# display.net
KiCad netlist of a schematic drawn in EAGLE
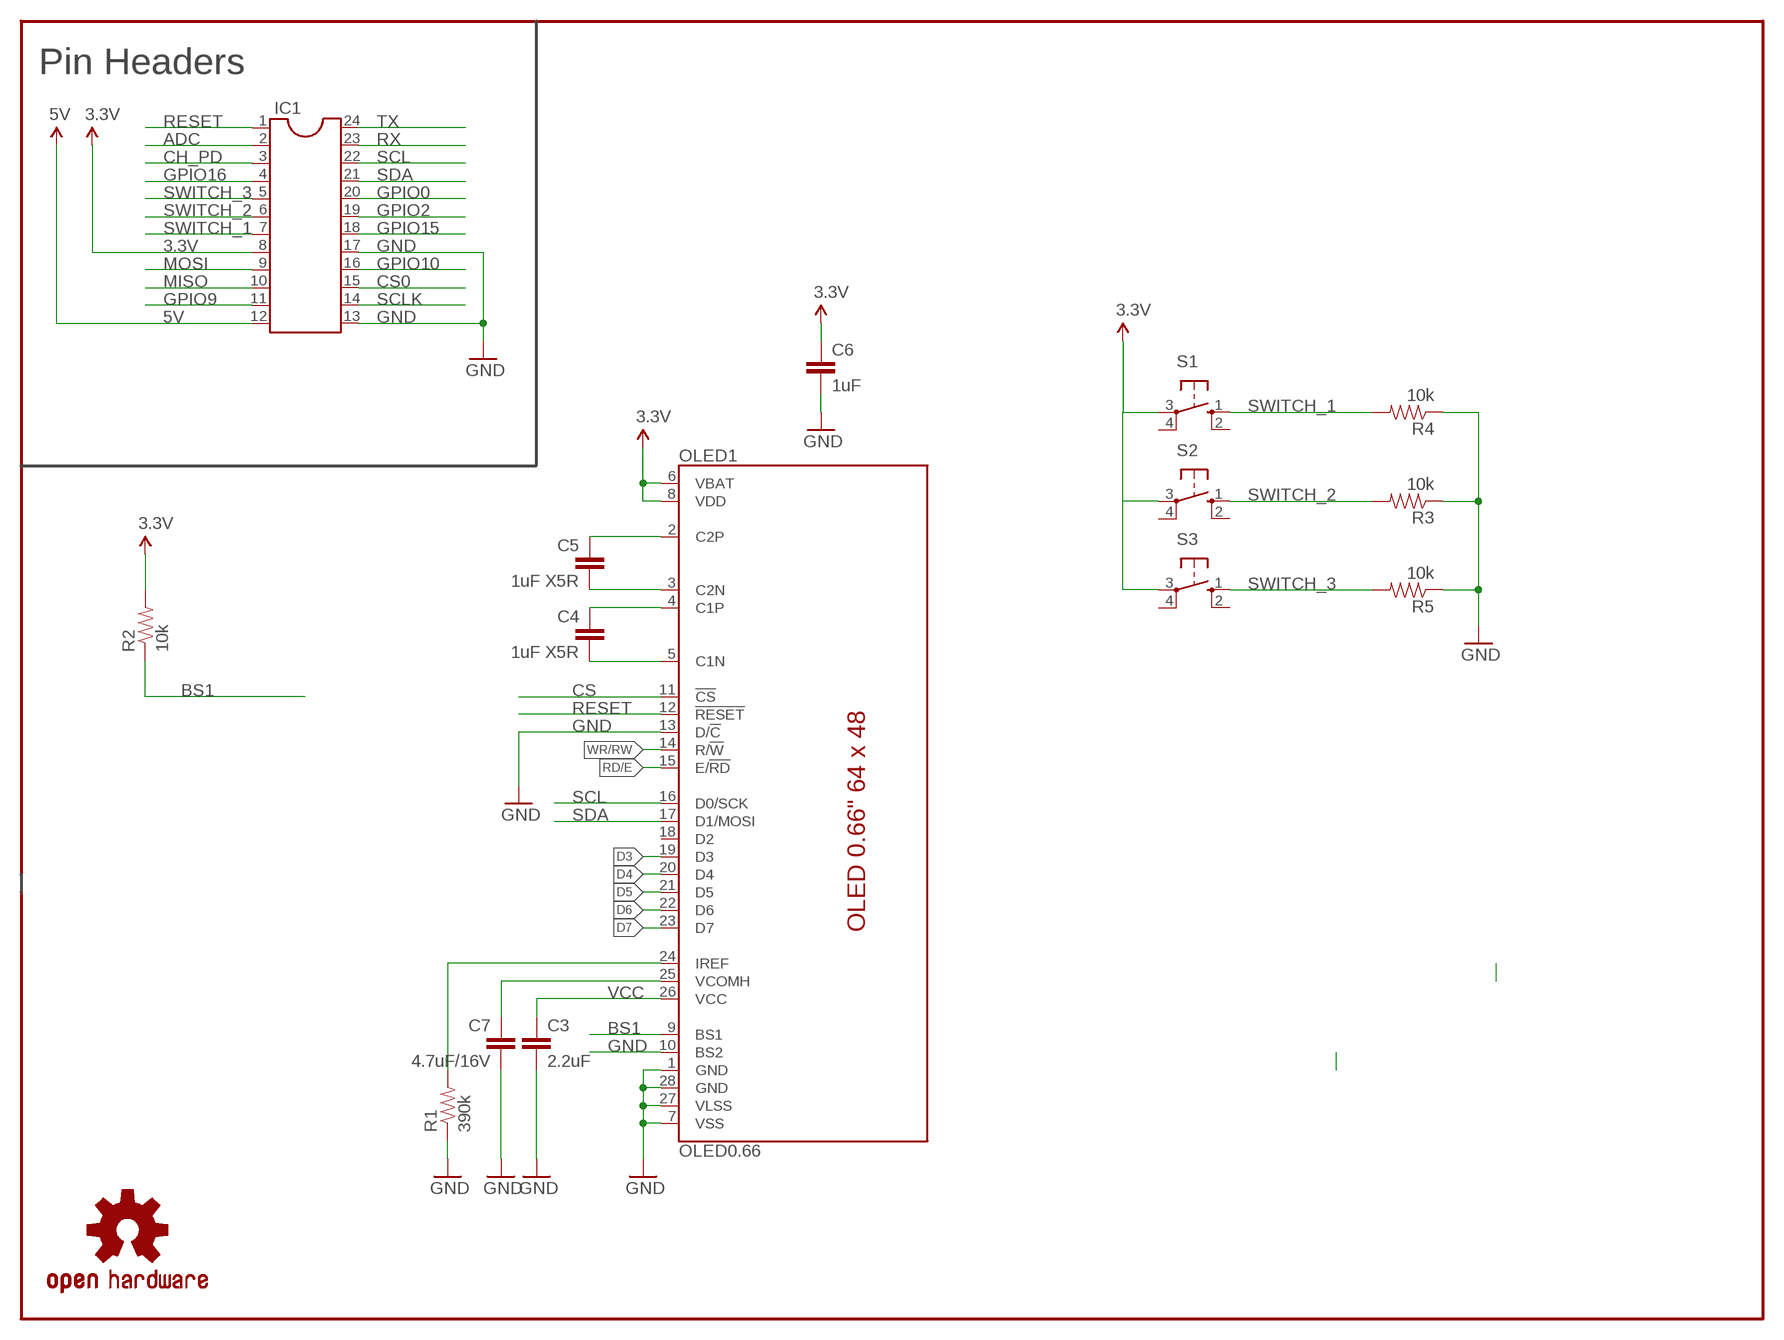
[diagram p0: schematic, sheet 1]

(export (version "E")
  (design (tool "Eeschema 10.0.6"))
  (components
    (comp (ref "C3")
      (value "2.2uF")
      (footprint "eagle-import:1206")
      (libsource (lib "eagle-import") (part "CAP1206"))
    )
    (comp (ref "C4")
      (value "1uF X5R")
      (footprint "eagle-import:1206")
      (libsource (lib "eagle-import") (part "CAP1206"))
    )
    (comp (ref "C5")
      (value "1uF X5R")
      (footprint "eagle-import:1206")
      (libsource (lib "eagle-import") (part "CAP1206"))
    )
    (comp (ref "C6")
      (value "1uF")
      (footprint "eagle-import:1206")
      (libsource (lib "eagle-import") (part "CAP1206"))
    )
    (comp (ref "C7")
      (value "4.7uF/16V")
      (footprint "eagle-import:1206")
      (libsource (lib "eagle-import") (part "CAP1206"))
    )
    (comp (ref "FRAME1")
      (value "FRAME-LETTERNO_PACKAGE")
      (footprint "eagle-import:DUMMY")
      (fields (field (name "DESIGNER") "Nobody"))
      (libsource (lib "eagle-import") (part "FRAME-LETTERNO_PACKAGE"))
    )
    (comp (ref "IC1")
      (value "DIL24-9")
      (footprint "eagle-import:DIL24-9")
      (libsource (lib "eagle-import") (part "DIL24-9"))
    )
    (comp (ref "LOGO1")
      (value "OSHW-LOGOS")
      (footprint "eagle-import:OSHW-LOGO-S")
      (libsource (lib "eagle-import") (part "OSHW-LOGOS"))
    )
    (comp (ref "OLED1")
      (value "OLED0.66")
      (footprint "eagle-import:OLED-0.66-64X48")
      (libsource (lib "eagle-import") (part "OLED0.66"))
    )
    (comp (ref "R1")
      (value "390k")
      (footprint "eagle-import:1206")
      (libsource (lib "eagle-import") (part "RESISTOR1206"))
    )
    (comp (ref "R2")
      (value "10k")
      (footprint "eagle-import:1206")
      (libsource (lib "eagle-import") (part "RESISTOR1206"))
    )
    (comp (ref "R3")
      (value "10k")
      (footprint "eagle-import:1206")
      (libsource (lib "eagle-import") (part "RESISTOR1206"))
    )
    (comp (ref "R4")
      (value "10k")
      (footprint "eagle-import:1206")
      (libsource (lib "eagle-import") (part "RESISTOR1206"))
    )
    (comp (ref "R5")
      (value "10k")
      (footprint "eagle-import:1206")
      (libsource (lib "eagle-import") (part "RESISTOR1206"))
    )
    (comp (ref "S1")
      (value "10-XX")
      (footprint "eagle-import:B3F-10XX")
      (fields (field (name "MPN") "B3F-1000"))
      (libsource (lib "eagle-import") (part "10-XX"))
    )
    (comp (ref "S2")
      (value "10-XX")
      (footprint "eagle-import:B3F-10XX")
      (fields (field (name "MPN") "B3F-1000"))
      (libsource (lib "eagle-import") (part "10-XX"))
    )
    (comp (ref "S3")
      (value "10-XX")
      (footprint "eagle-import:B3F-10XX")
      (fields (field (name "MPN") "B3F-1000"))
      (libsource (lib "eagle-import") (part "10-XX"))
    )
  )
  (nets
    (net (code "1") (name "/ADC") (class "Default")
      (node (ref "IC1") (pin "2") (pinfunction "2_2") (pintype "passive"))
    )
    (net (code "2") (name "/BS1") (class "Default")
      (node (ref "OLED1") (pin "9") (pinfunction "BS1_9") (pintype "bidirectional"))
      (node (ref "R2") (pin "1") (pinfunction "1_1") (pintype "passive"))
    )
    (net (code "3") (name "/CH_PD") (class "Default")
      (node (ref "IC1") (pin "3") (pinfunction "3_3") (pintype "passive"))
    )
    (net (code "4") (name "/CS") (class "Default")
      (node (ref "OLED1") (pin "11") (pinfunction "~{CS}_11") (pintype "bidirectional"))
    )
    (net (code "5") (name "/CS0") (class "Default")
      (node (ref "IC1") (pin "15") (pinfunction "15_15") (pintype "passive"))
    )
    (net (code "6") (name "/GPIO0") (class "Default")
      (node (ref "IC1") (pin "20") (pinfunction "20_20") (pintype "passive"))
    )
    (net (code "7") (name "/GPIO2") (class "Default")
      (node (ref "IC1") (pin "19") (pinfunction "19_19") (pintype "passive"))
    )
    (net (code "8") (name "/GPIO9") (class "Default")
      (node (ref "IC1") (pin "11") (pinfunction "11_11") (pintype "passive"))
    )
    (net (code "9") (name "/GPIO10") (class "Default")
      (node (ref "IC1") (pin "16") (pinfunction "16_16") (pintype "passive"))
    )
    (net (code "10") (name "/GPIO15") (class "Default")
      (node (ref "IC1") (pin "18") (pinfunction "18_18") (pintype "passive"))
    )
    (net (code "11") (name "/GPIO16") (class "Default")
      (node (ref "IC1") (pin "4") (pinfunction "4_4") (pintype "passive"))
    )
    (net (code "12") (name "/MISO") (class "Default")
      (node (ref "IC1") (pin "10") (pinfunction "10_10") (pintype "passive"))
    )
    (net (code "13") (name "/MOSI") (class "Default")
      (node (ref "IC1") (pin "9") (pinfunction "9_9") (pintype "passive"))
    )
    (net (code "14") (name "/RESET") (class "Default")
      (node (ref "IC1") (pin "1") (pinfunction "1_1") (pintype "passive"))
      (node (ref "OLED1") (pin "12") (pinfunction "~{RESET}_12") (pintype "bidirectional"))
    )
    (net (code "15") (name "/RX") (class "Default")
      (node (ref "IC1") (pin "23") (pinfunction "23_23") (pintype "passive"))
    )
    (net (code "16") (name "/SCL") (class "Default")
      (node (ref "IC1") (pin "22") (pinfunction "22_22") (pintype "passive"))
      (node (ref "OLED1") (pin "16") (pinfunction "D0/SCK_16") (pintype "bidirectional"))
    )
    (net (code "17") (name "/SCLK") (class "Default")
      (node (ref "IC1") (pin "14") (pinfunction "14_14") (pintype "passive"))
    )
    (net (code "18") (name "/SDA") (class "Default")
      (node (ref "IC1") (pin "21") (pinfunction "21_21") (pintype "passive"))
      (node (ref "OLED1") (pin "17") (pinfunction "D1/MOSI_17") (pintype "bidirectional"))
    )
    (net (code "19") (name "/SWITCH_1") (class "Default")
      (node (ref "IC1") (pin "7") (pinfunction "7_7") (pintype "passive"))
      (node (ref "R4") (pin "2") (pinfunction "2_2") (pintype "passive"))
      (node (ref "S1") (pin "1") (pinfunction "S_1") (pintype "passive"))
    )
    (net (code "20") (name "/SWITCH_2") (class "Default")
      (node (ref "IC1") (pin "6") (pinfunction "6_6") (pintype "passive"))
      (node (ref "R3") (pin "2") (pinfunction "2_2") (pintype "passive"))
      (node (ref "S2") (pin "1") (pinfunction "S_1") (pintype "passive"))
    )
    (net (code "21") (name "/SWITCH_3") (class "Default")
      (node (ref "IC1") (pin "5") (pinfunction "5_5") (pintype "passive"))
      (node (ref "R5") (pin "2") (pinfunction "2_2") (pintype "passive"))
      (node (ref "S3") (pin "1") (pinfunction "S_1") (pintype "passive"))
    )
    (net (code "22") (name "/TX") (class "Default")
      (node (ref "IC1") (pin "24") (pinfunction "24_24") (pintype "passive"))
    )
    (net (code "23") (name "/VCC") (class "Default")
      (node (ref "C3") (pin "1") (pinfunction "1_1") (pintype "passive"))
      (node (ref "OLED1") (pin "26") (pinfunction "VCC_26") (pintype "bidirectional"))
    )
    (net (code "24") (name "3.3V") (class "Default")
      (node (ref "C6") (pin "1") (pinfunction "1_1") (pintype "passive"))
      (node (ref "IC1") (pin "8") (pinfunction "8_8") (pintype "passive"))
      (node (ref "OLED1") (pin "6") (pinfunction "VBAT_6") (pintype "bidirectional"))
      (node (ref "OLED1") (pin "8") (pinfunction "VDD_8") (pintype "bidirectional"))
      (node (ref "R2") (pin "2") (pinfunction "2_2") (pintype "passive"))
      (node (ref "S1") (pin "3") (pinfunction "P_3") (pintype "passive"))
      (node (ref "S2") (pin "3") (pinfunction "P_3") (pintype "passive"))
      (node (ref "S3") (pin "3") (pinfunction "P_3") (pintype "passive"))
    )
    (net (code "25") (name "5V") (class "Default")
      (node (ref "IC1") (pin "12") (pinfunction "12_12") (pintype "passive"))
    )
    (net (code "26") (name "D3") (class "Default")
      (node (ref "OLED1") (pin "19") (pinfunction "D3_19") (pintype "bidirectional"))
    )
    (net (code "27") (name "D4") (class "Default")
      (node (ref "OLED1") (pin "20") (pinfunction "D4_20") (pintype "bidirectional"))
    )
    (net (code "28") (name "D5") (class "Default")
      (node (ref "OLED1") (pin "21") (pinfunction "D5_21") (pintype "bidirectional"))
    )
    (net (code "29") (name "D6") (class "Default")
      (node (ref "OLED1") (pin "22") (pinfunction "D6_22") (pintype "bidirectional"))
    )
    (net (code "30") (name "D7") (class "Default")
      (node (ref "OLED1") (pin "23") (pinfunction "D7_23") (pintype "bidirectional"))
    )
    (net (code "31") (name "GND") (class "Default")
      (node (ref "C3") (pin "2") (pinfunction "2_2") (pintype "passive"))
      (node (ref "C6") (pin "2") (pinfunction "2_2") (pintype "passive"))
      (node (ref "C7") (pin "2") (pinfunction "2_2") (pintype "passive"))
      (node (ref "IC1") (pin "13") (pinfunction "13_13") (pintype "passive"))
      (node (ref "IC1") (pin "17") (pinfunction "17_17") (pintype "passive"))
      (node (ref "OLED1") (pin "1") (pinfunction "GND_1") (pintype "bidirectional"))
      (node (ref "OLED1") (pin "10") (pinfunction "BS2_10") (pintype "bidirectional"))
      (node (ref "OLED1") (pin "13") (pinfunction "D/~{C}_13") (pintype "bidirectional"))
      (node (ref "OLED1") (pin "27") (pinfunction "VLSS_27") (pintype "bidirectional"))
      (node (ref "OLED1") (pin "28") (pinfunction "GND_28") (pintype "bidirectional"))
      (node (ref "OLED1") (pin "7") (pinfunction "VSS_7") (pintype "bidirectional"))
      (node (ref "R1") (pin "1") (pinfunction "1_1") (pintype "passive"))
      (node (ref "R3") (pin "1") (pinfunction "1_1") (pintype "passive"))
      (node (ref "R4") (pin "1") (pinfunction "1_1") (pintype "passive"))
      (node (ref "R5") (pin "1") (pinfunction "1_1") (pintype "passive"))
    )
    (net (code "32") (name "Net-(OLED1-C1N)") (class "Default")
      (node (ref "C4") (pin "2") (pinfunction "2_2") (pintype "passive"))
      (node (ref "OLED1") (pin "5") (pinfunction "C1N_5") (pintype "bidirectional"))
    )
    (net (code "33") (name "Net-(OLED1-C1P)") (class "Default")
      (node (ref "C4") (pin "1") (pinfunction "1_1") (pintype "passive"))
      (node (ref "OLED1") (pin "4") (pinfunction "C1P_4") (pintype "bidirectional"))
    )
    (net (code "34") (name "Net-(OLED1-C2N)") (class "Default")
      (node (ref "C5") (pin "2") (pinfunction "2_2") (pintype "passive"))
      (node (ref "OLED1") (pin "3") (pinfunction "C2N_3") (pintype "bidirectional"))
    )
    (net (code "35") (name "Net-(OLED1-C2P)") (class "Default")
      (node (ref "C5") (pin "1") (pinfunction "1_1") (pintype "passive"))
      (node (ref "OLED1") (pin "2") (pinfunction "C2P_2") (pintype "bidirectional"))
    )
    (net (code "36") (name "Net-(OLED1-IREF)") (class "Default")
      (node (ref "OLED1") (pin "24") (pinfunction "IREF_24") (pintype "bidirectional"))
      (node (ref "R1") (pin "2") (pinfunction "2_2") (pintype "passive"))
    )
    (net (code "37") (name "Net-(OLED1-VCOMH)") (class "Default")
      (node (ref "C7") (pin "1") (pinfunction "1_1") (pintype "passive"))
      (node (ref "OLED1") (pin "25") (pinfunction "VCOMH_25") (pintype "bidirectional"))
    )
    (net (code "38") (name "RD{slash}E") (class "Default")
      (node (ref "OLED1") (pin "15") (pinfunction "E/~{RD}_15") (pintype "bidirectional"))
    )
    (net (code "39") (name "WR{slash}RW") (class "Default")
      (node (ref "OLED1") (pin "14") (pinfunction "R/~{W}_14") (pintype "bidirectional"))
    )
    (net (code "40") (name "unconnected-(OLED1-D2-Pad18)") (class "Default")
      (node (ref "OLED1") (pin "18") (pinfunction "D2_18") (pintype "bidirectional"))
    )
    (net (code "41") (name "unconnected-(S1-P1-Pad4)") (class "Default")
      (node (ref "S1") (pin "4") (pinfunction "P1_4") (pintype "passive"))
    )
    (net (code "42") (name "unconnected-(S1-S1-Pad2)") (class "Default")
      (node (ref "S1") (pin "2") (pinfunction "S1_2") (pintype "passive"))
    )
    (net (code "43") (name "unconnected-(S2-P1-Pad4)") (class "Default")
      (node (ref "S2") (pin "4") (pinfunction "P1_4") (pintype "passive"))
    )
    (net (code "44") (name "unconnected-(S2-S1-Pad2)") (class "Default")
      (node (ref "S2") (pin "2") (pinfunction "S1_2") (pintype "passive"))
    )
    (net (code "45") (name "unconnected-(S3-P1-Pad4)") (class "Default")
      (node (ref "S3") (pin "4") (pinfunction "P1_4") (pintype "passive"))
    )
    (net (code "46") (name "unconnected-(S3-S1-Pad2)") (class "Default")
      (node (ref "S3") (pin "2") (pinfunction "S1_2") (pintype "passive"))
    )
  )
)
